# NavCom_Board_1.net
KiCad netlist of a schematic drawn in EAGLE
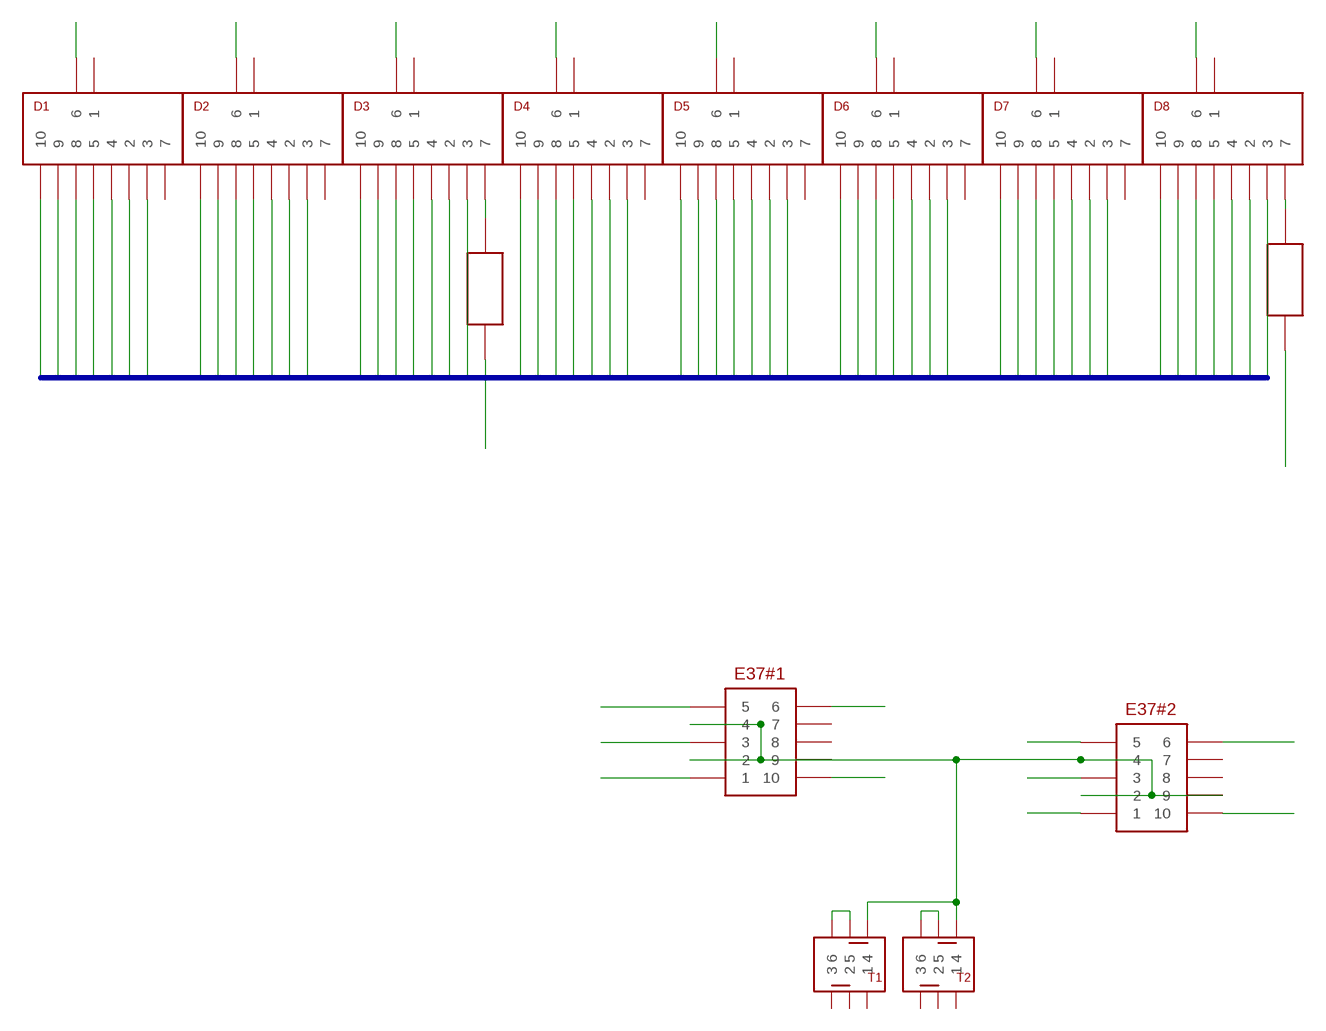
[diagram p0: schematic, sheet 1, part 1 of 2]
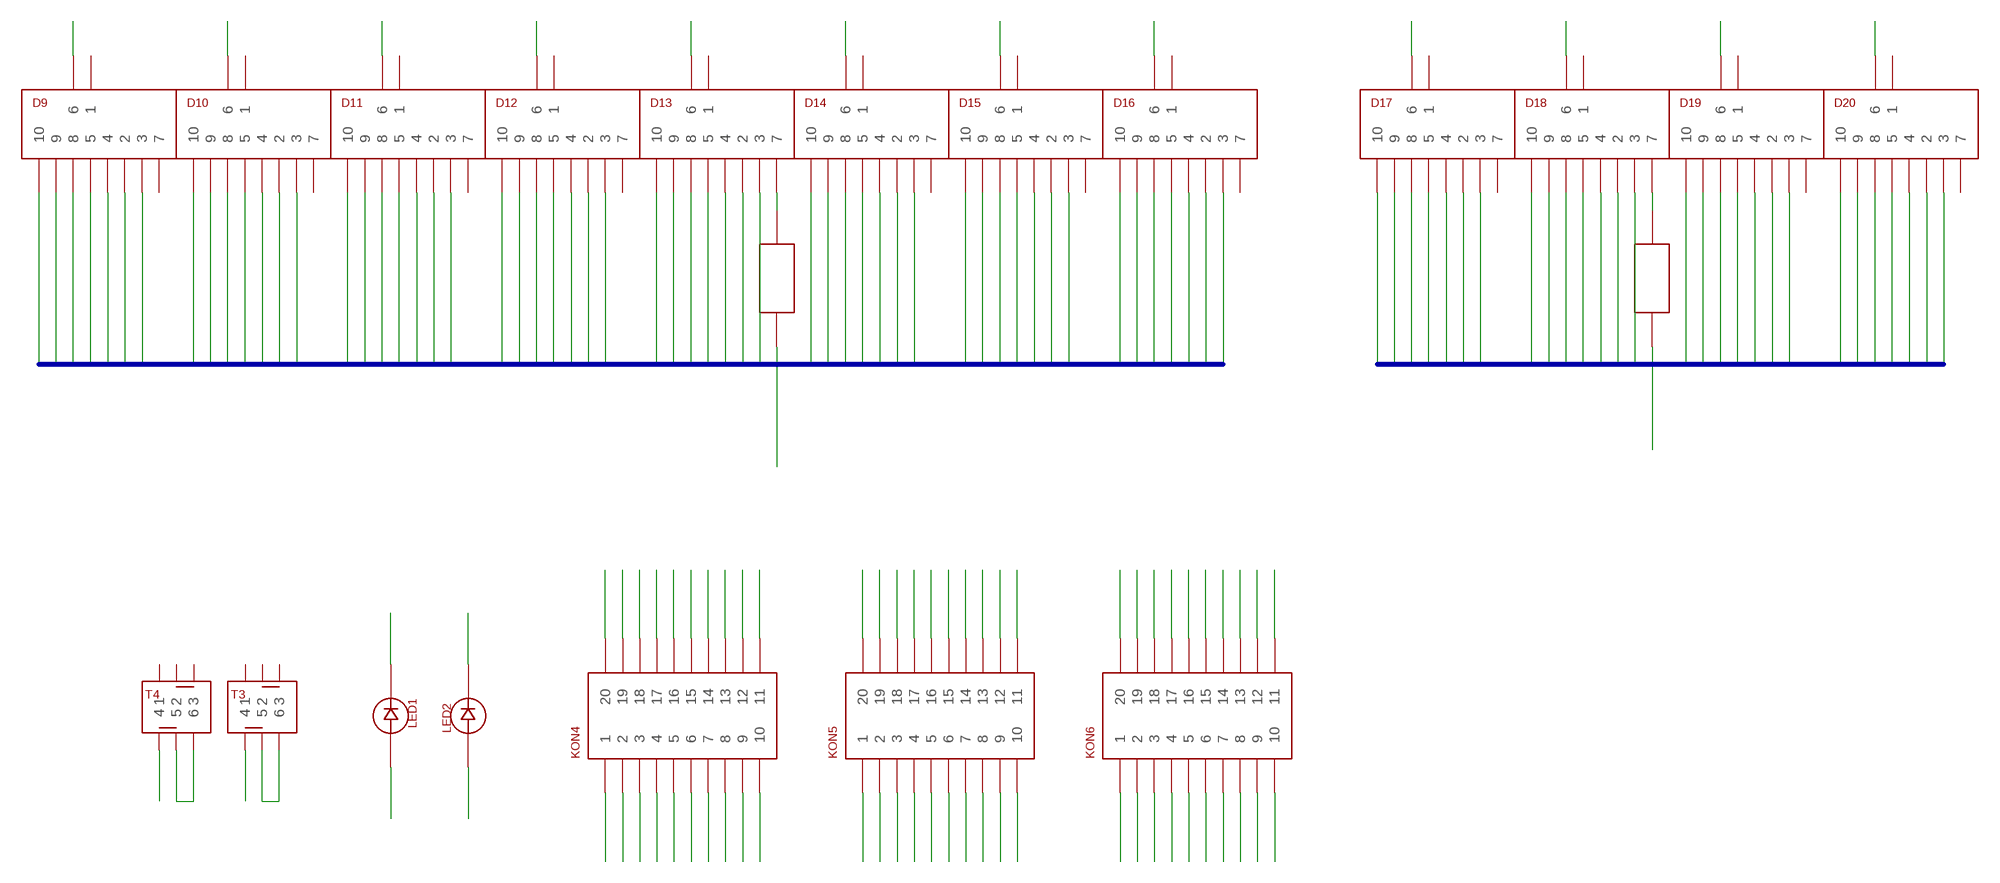
[diagram p1: schematic, sheet 1, part 2 of 2]

(export (version "E")
  (design (tool "Eeschema 10.0.6"))
  (components
    (comp (ref "D1")
      (value "SA3611EWA")
      (footprint "eagle-import:SA3611EWA")
      (libsource (lib "eagle-import") (part "SA3611EWA"))
    )
    (comp (ref "D2")
      (value "SA3611EWA")
      (footprint "eagle-import:SA3611EWA")
      (libsource (lib "eagle-import") (part "SA3611EWA"))
    )
    (comp (ref "D3")
      (value "SA3611EWA")
      (footprint "eagle-import:SA3611EWA")
      (libsource (lib "eagle-import") (part "SA3611EWA"))
    )
    (comp (ref "D4")
      (value "SA3611EWA")
      (footprint "eagle-import:SA3611EWA")
      (libsource (lib "eagle-import") (part "SA3611EWA"))
    )
    (comp (ref "D5")
      (value "SA3611EWA")
      (footprint "eagle-import:SA3611EWA")
      (libsource (lib "eagle-import") (part "SA3611EWA"))
    )
    (comp (ref "D6")
      (value "SA3611EWA")
      (footprint "eagle-import:SA3611EWA")
      (libsource (lib "eagle-import") (part "SA3611EWA"))
    )
    (comp (ref "D7")
      (value "SA3611EWA")
      (footprint "eagle-import:SA3611EWA")
      (libsource (lib "eagle-import") (part "SA3611EWA"))
    )
    (comp (ref "D8")
      (value "SA3611EWA")
      (footprint "eagle-import:SA3611EWA")
      (libsource (lib "eagle-import") (part "SA3611EWA"))
    )
    (comp (ref "D9")
      (value "SA3611EWA")
      (footprint "eagle-import:SA3611EWA")
      (libsource (lib "eagle-import") (part "SA3611EWA"))
    )
    (comp (ref "D10")
      (value "SA3611EWA")
      (footprint "eagle-import:SA3611EWA")
      (libsource (lib "eagle-import") (part "SA3611EWA"))
    )
    (comp (ref "D11")
      (value "SA3611EWA")
      (footprint "eagle-import:SA3611EWA")
      (libsource (lib "eagle-import") (part "SA3611EWA"))
    )
    (comp (ref "D12")
      (value "SA3611EWA")
      (footprint "eagle-import:SA3611EWA")
      (libsource (lib "eagle-import") (part "SA3611EWA"))
    )
    (comp (ref "D13")
      (value "SA3611EWA")
      (footprint "eagle-import:SA3611EWA")
      (libsource (lib "eagle-import") (part "SA3611EWA"))
    )
    (comp (ref "D14")
      (value "SA3611EWA")
      (footprint "eagle-import:SA3611EWA")
      (libsource (lib "eagle-import") (part "SA3611EWA"))
    )
    (comp (ref "D15")
      (value "SA3611EWA")
      (footprint "eagle-import:SA3611EWA")
      (libsource (lib "eagle-import") (part "SA3611EWA"))
    )
    (comp (ref "D16")
      (value "SA3611EWA")
      (footprint "eagle-import:SA3611EWA")
      (libsource (lib "eagle-import") (part "SA3611EWA"))
    )
    (comp (ref "D17")
      (value "SA3611EWA")
      (footprint "eagle-import:SA3611EWA")
      (libsource (lib "eagle-import") (part "SA3611EWA"))
    )
    (comp (ref "D18")
      (value "SA3611EWA")
      (footprint "eagle-import:SA3611EWA")
      (libsource (lib "eagle-import") (part "SA3611EWA"))
    )
    (comp (ref "D19")
      (value "SA3611EWA")
      (footprint "eagle-import:SA3611EWA")
      (libsource (lib "eagle-import") (part "SA3611EWA"))
    )
    (comp (ref "D20")
      (value "SA3611EWA")
      (footprint "eagle-import:SA3611EWA")
      (libsource (lib "eagle-import") (part "SA3611EWA"))
    )
    (comp (ref "E37#1")
      (value "ELMA_E37")
      (footprint "eagle-import:ELMA_E37")
      (libsource (lib "eagle-import") (part "ELMA_E37"))
    )
    (comp (ref "E37#2")
      (value "ELMA_E37")
      (footprint "eagle-import:ELMA_E37")
      (libsource (lib "eagle-import") (part "ELMA_E37"))
    )
    (comp (ref "KON4")
      (value "LISTA_2X10")
      (footprint "eagle-import:LISTA_2X10")
      (libsource (lib "eagle-import") (part "LISTA_2X10"))
    )
    (comp (ref "KON5")
      (value "LISTA_2X10")
      (footprint "eagle-import:LISTA_2X10")
      (libsource (lib "eagle-import") (part "LISTA_2X10"))
    )
    (comp (ref "KON6")
      (value "LISTA_2X10")
      (footprint "eagle-import:LISTA_2X10")
      (libsource (lib "eagle-import") (part "LISTA_2X10"))
    )
    (comp (ref "LED1")
      (value "LED_5MM")
      (footprint "eagle-import:LED_5MM")
      (libsource (lib "eagle-import") (part "LED_5MM"))
    )
    (comp (ref "LED2")
      (value "LED_5MM")
      (footprint "eagle-import:LED_5MM")
      (libsource (lib "eagle-import") (part "LED_5MM"))
    )
    (comp (ref "T1")
      (value "P1-0S")
      (footprint "eagle-import:P1-0S")
      (libsource (lib "eagle-import") (part "P1-0S"))
    )
    (comp (ref "T2")
      (value "P1-0S")
      (footprint "eagle-import:P1-0S")
      (libsource (lib "eagle-import") (part "P1-0S"))
    )
    (comp (ref "T3")
      (value "P1-0S")
      (footprint "eagle-import:P1-0S")
      (libsource (lib "eagle-import") (part "P1-0S"))
    )
    (comp (ref "T4")
      (value "P1-0S")
      (footprint "eagle-import:P1-0S")
      (libsource (lib "eagle-import") (part "P1-0S"))
    )
    (comp (ref "U$1")
      (value "REZISTOR")
      (footprint "eagle-import:REZISTOR")
      (libsource (lib "eagle-import") (part "REZISTOR"))
    )
    (comp (ref "U$2")
      (value "REZISTOR")
      (footprint "eagle-import:REZISTOR")
      (libsource (lib "eagle-import") (part "REZISTOR"))
    )
    (comp (ref "U$3")
      (value "REZISTOR")
      (footprint "eagle-import:REZISTOR")
      (libsource (lib "eagle-import") (part "REZISTOR"))
    )
    (comp (ref "U$4")
      (value "REZISTOR")
      (footprint "eagle-import:REZISTOR")
      (libsource (lib "eagle-import") (part "REZISTOR"))
    )
  )
  (nets
    (net (code "1") (name "/D1") (class "Default")
      (node (ref "D1") (pin "6") (pinfunction "6_6") (pintype "bidirectional"))
      (node (ref "KON4") (pin "1") (pinfunction "1_1") (pintype "bidirectional"))
    )
    (net (code "2") (name "/D2") (class "Default")
      (node (ref "D2") (pin "6") (pinfunction "6_6") (pintype "bidirectional"))
      (node (ref "KON4") (pin "2") (pinfunction "2_2") (pintype "bidirectional"))
    )
    (net (code "3") (name "/D3") (class "Default")
      (node (ref "D3") (pin "6") (pinfunction "6_6") (pintype "bidirectional"))
      (node (ref "KON4") (pin "9") (pinfunction "9_9") (pintype "bidirectional"))
    )
    (net (code "4") (name "/D4") (class "Default")
      (node (ref "D4") (pin "6") (pinfunction "6_6") (pintype "bidirectional"))
      (node (ref "KON4") (pin "6") (pinfunction "6_6") (pintype "bidirectional"))
    )
    (net (code "5") (name "/D5") (class "Default")
      (node (ref "D5") (pin "6") (pinfunction "6_6") (pintype "bidirectional"))
      (node (ref "KON4") (pin "3") (pinfunction "3_3") (pintype "bidirectional"))
    )
    (net (code "6") (name "/D6") (class "Default")
      (node (ref "D6") (pin "6") (pinfunction "6_6") (pintype "bidirectional"))
      (node (ref "KON4") (pin "8") (pinfunction "8_8") (pintype "bidirectional"))
    )
    (net (code "7") (name "/D7") (class "Default")
      (node (ref "D7") (pin "6") (pinfunction "6_6") (pintype "bidirectional"))
      (node (ref "KON4") (pin "7") (pinfunction "7_7") (pintype "bidirectional"))
    )
    (net (code "8") (name "/D8") (class "Default")
      (node (ref "D8") (pin "6") (pinfunction "6_6") (pintype "bidirectional"))
      (node (ref "KON4") (pin "4") (pinfunction "4_4") (pintype "bidirectional"))
    )
    (net (code "9") (name "/D9") (class "Default")
      (node (ref "D9") (pin "6") (pinfunction "6_6") (pintype "bidirectional"))
      (node (ref "KON5") (pin "1") (pinfunction "1_1") (pintype "bidirectional"))
    )
    (net (code "10") (name "/D10") (class "Default")
      (node (ref "D10") (pin "6") (pinfunction "6_6") (pintype "bidirectional"))
      (node (ref "KON5") (pin "2") (pinfunction "2_2") (pintype "bidirectional"))
    )
    (net (code "11") (name "/D11") (class "Default")
      (node (ref "D11") (pin "6") (pinfunction "6_6") (pintype "bidirectional"))
      (node (ref "KON5") (pin "9") (pinfunction "9_9") (pintype "bidirectional"))
    )
    (net (code "12") (name "/D12") (class "Default")
      (node (ref "D12") (pin "6") (pinfunction "6_6") (pintype "bidirectional"))
      (node (ref "KON5") (pin "6") (pinfunction "6_6") (pintype "bidirectional"))
    )
    (net (code "13") (name "/D13") (class "Default")
      (node (ref "D13") (pin "6") (pinfunction "6_6") (pintype "bidirectional"))
      (node (ref "KON5") (pin "3") (pinfunction "3_3") (pintype "bidirectional"))
    )
    (net (code "14") (name "/D14") (class "Default")
      (node (ref "D14") (pin "6") (pinfunction "6_6") (pintype "bidirectional"))
      (node (ref "KON5") (pin "8") (pinfunction "8_8") (pintype "bidirectional"))
    )
    (net (code "15") (name "/D15") (class "Default")
      (node (ref "D15") (pin "6") (pinfunction "6_6") (pintype "bidirectional"))
      (node (ref "KON5") (pin "7") (pinfunction "7_7") (pintype "bidirectional"))
    )
    (net (code "16") (name "/D16") (class "Default")
      (node (ref "D16") (pin "6") (pinfunction "6_6") (pintype "bidirectional"))
      (node (ref "KON5") (pin "4") (pinfunction "4_4") (pintype "bidirectional"))
    )
    (net (code "17") (name "/D17") (class "Default")
      (node (ref "D17") (pin "6") (pinfunction "6_6") (pintype "bidirectional"))
      (node (ref "KON6") (pin "1") (pinfunction "1_1") (pintype "bidirectional"))
    )
    (net (code "18") (name "/D18") (class "Default")
      (node (ref "D18") (pin "6") (pinfunction "6_6") (pintype "bidirectional"))
      (node (ref "KON6") (pin "2") (pinfunction "2_2") (pintype "bidirectional"))
    )
    (net (code "19") (name "/D19") (class "Default")
      (node (ref "D19") (pin "6") (pinfunction "6_6") (pintype "bidirectional"))
      (node (ref "KON6") (pin "9") (pinfunction "9_9") (pintype "bidirectional"))
    )
    (net (code "20") (name "/D20") (class "Default")
      (node (ref "D20") (pin "6") (pinfunction "6_6") (pintype "bidirectional"))
      (node (ref "KON6") (pin "6") (pinfunction "6_6") (pintype "bidirectional"))
    )
    (net (code "21") (name "/DRIVER1_SEG2") (class "Default")
      (node (ref "D1") (pin "2") (pinfunction "2_2") (pintype "bidirectional"))
      (node (ref "D2") (pin "2") (pinfunction "2_2") (pintype "bidirectional"))
      (node (ref "D3") (pin "2") (pinfunction "2_2") (pintype "bidirectional"))
      (node (ref "D4") (pin "2") (pinfunction "2_2") (pintype "bidirectional"))
      (node (ref "D5") (pin "2") (pinfunction "2_2") (pintype "bidirectional"))
      (node (ref "D6") (pin "2") (pinfunction "2_2") (pintype "bidirectional"))
      (node (ref "D7") (pin "2") (pinfunction "2_2") (pintype "bidirectional"))
      (node (ref "D8") (pin "2") (pinfunction "2_2") (pintype "bidirectional"))
      (node (ref "KON4") (pin "10") (pinfunction "10_10") (pintype "bidirectional"))
    )
    (net (code "22") (name "/DRIVER1_SEG3") (class "Default")
      (node (ref "D1") (pin "3") (pinfunction "3_3") (pintype "bidirectional"))
      (node (ref "D2") (pin "3") (pinfunction "3_3") (pintype "bidirectional"))
      (node (ref "D3") (pin "3") (pinfunction "3_3") (pintype "bidirectional"))
      (node (ref "D4") (pin "3") (pinfunction "3_3") (pintype "bidirectional"))
      (node (ref "D5") (pin "3") (pinfunction "3_3") (pintype "bidirectional"))
      (node (ref "D6") (pin "3") (pinfunction "3_3") (pintype "bidirectional"))
      (node (ref "D7") (pin "3") (pinfunction "3_3") (pintype "bidirectional"))
      (node (ref "D8") (pin "3") (pinfunction "3_3") (pintype "bidirectional"))
      (node (ref "KON4") (pin "12") (pinfunction "12_12") (pintype "bidirectional"))
    )
    (net (code "23") (name "/DRIVER1_SEG4") (class "Default")
      (node (ref "D1") (pin "4") (pinfunction "4_4") (pintype "bidirectional"))
      (node (ref "D2") (pin "4") (pinfunction "4_4") (pintype "bidirectional"))
      (node (ref "D3") (pin "4") (pinfunction "4_4") (pintype "bidirectional"))
      (node (ref "D4") (pin "4") (pinfunction "4_4") (pintype "bidirectional"))
      (node (ref "D5") (pin "4") (pinfunction "4_4") (pintype "bidirectional"))
      (node (ref "D6") (pin "4") (pinfunction "4_4") (pintype "bidirectional"))
      (node (ref "D7") (pin "4") (pinfunction "4_4") (pintype "bidirectional"))
      (node (ref "D8") (pin "4") (pinfunction "4_4") (pintype "bidirectional"))
      (node (ref "KON4") (pin "15") (pinfunction "15_15") (pintype "bidirectional"))
    )
    (net (code "24") (name "/DRIVER1_SEG5") (class "Default")
      (node (ref "D1") (pin "5") (pinfunction "5_5") (pintype "bidirectional"))
      (node (ref "D2") (pin "5") (pinfunction "5_5") (pintype "bidirectional"))
      (node (ref "D3") (pin "5") (pinfunction "5_5") (pintype "bidirectional"))
      (node (ref "D4") (pin "5") (pinfunction "5_5") (pintype "bidirectional"))
      (node (ref "D5") (pin "5") (pinfunction "5_5") (pintype "bidirectional"))
      (node (ref "D6") (pin "5") (pinfunction "5_5") (pintype "bidirectional"))
      (node (ref "D7") (pin "5") (pinfunction "5_5") (pintype "bidirectional"))
      (node (ref "D8") (pin "5") (pinfunction "5_5") (pintype "bidirectional"))
      (node (ref "KON4") (pin "16") (pinfunction "16_16") (pintype "bidirectional"))
    )
    (net (code "25") (name "/DRIVER1_SEG8") (class "Default")
      (node (ref "D1") (pin "8") (pinfunction "8_8") (pintype "bidirectional"))
      (node (ref "D2") (pin "8") (pinfunction "8_8") (pintype "bidirectional"))
      (node (ref "D3") (pin "8") (pinfunction "8_8") (pintype "bidirectional"))
      (node (ref "D4") (pin "8") (pinfunction "8_8") (pintype "bidirectional"))
      (node (ref "D5") (pin "8") (pinfunction "8_8") (pintype "bidirectional"))
      (node (ref "D6") (pin "8") (pinfunction "8_8") (pintype "bidirectional"))
      (node (ref "D7") (pin "8") (pinfunction "8_8") (pintype "bidirectional"))
      (node (ref "D8") (pin "8") (pinfunction "8_8") (pintype "bidirectional"))
      (node (ref "KON4") (pin "14") (pinfunction "14_14") (pintype "bidirectional"))
    )
    (net (code "26") (name "/DRIVER1_SEG9") (class "Default")
      (node (ref "D1") (pin "9") (pinfunction "9_9") (pintype "bidirectional"))
      (node (ref "D2") (pin "9") (pinfunction "9_9") (pintype "bidirectional"))
      (node (ref "D3") (pin "9") (pinfunction "9_9") (pintype "bidirectional"))
      (node (ref "D4") (pin "9") (pinfunction "9_9") (pintype "bidirectional"))
      (node (ref "D5") (pin "9") (pinfunction "9_9") (pintype "bidirectional"))
      (node (ref "D6") (pin "9") (pinfunction "9_9") (pintype "bidirectional"))
      (node (ref "D7") (pin "9") (pinfunction "9_9") (pintype "bidirectional"))
      (node (ref "D8") (pin "9") (pinfunction "9_9") (pintype "bidirectional"))
      (node (ref "KON4") (pin "11") (pinfunction "11_11") (pintype "bidirectional"))
    )
    (net (code "27") (name "/DRIVER1_SEG10") (class "Default")
      (node (ref "D1") (pin "10") (pinfunction "10_10") (pintype "bidirectional"))
      (node (ref "D2") (pin "10") (pinfunction "10_10") (pintype "bidirectional"))
      (node (ref "D3") (pin "10") (pinfunction "10_10") (pintype "bidirectional"))
      (node (ref "D4") (pin "10") (pinfunction "10_10") (pintype "bidirectional"))
      (node (ref "D5") (pin "10") (pinfunction "10_10") (pintype "bidirectional"))
      (node (ref "D6") (pin "10") (pinfunction "10_10") (pintype "bidirectional"))
      (node (ref "D7") (pin "10") (pinfunction "10_10") (pintype "bidirectional"))
      (node (ref "D8") (pin "10") (pinfunction "10_10") (pintype "bidirectional"))
      (node (ref "KON4") (pin "13") (pinfunction "13_13") (pintype "bidirectional"))
    )
    (net (code "28") (name "/DRIVER2_SEG2") (class "Default")
      (node (ref "D10") (pin "2") (pinfunction "2_2") (pintype "bidirectional"))
      (node (ref "D11") (pin "2") (pinfunction "2_2") (pintype "bidirectional"))
      (node (ref "D12") (pin "2") (pinfunction "2_2") (pintype "bidirectional"))
      (node (ref "D13") (pin "2") (pinfunction "2_2") (pintype "bidirectional"))
      (node (ref "D14") (pin "2") (pinfunction "2_2") (pintype "bidirectional"))
      (node (ref "D15") (pin "2") (pinfunction "2_2") (pintype "bidirectional"))
      (node (ref "D16") (pin "2") (pinfunction "2_2") (pintype "bidirectional"))
      (node (ref "D9") (pin "2") (pinfunction "2_2") (pintype "bidirectional"))
      (node (ref "KON5") (pin "10") (pinfunction "10_10") (pintype "bidirectional"))
    )
    (net (code "29") (name "/DRIVER2_SEG3") (class "Default")
      (node (ref "D10") (pin "3") (pinfunction "3_3") (pintype "bidirectional"))
      (node (ref "D11") (pin "3") (pinfunction "3_3") (pintype "bidirectional"))
      (node (ref "D12") (pin "3") (pinfunction "3_3") (pintype "bidirectional"))
      (node (ref "D13") (pin "3") (pinfunction "3_3") (pintype "bidirectional"))
      (node (ref "D14") (pin "3") (pinfunction "3_3") (pintype "bidirectional"))
      (node (ref "D15") (pin "3") (pinfunction "3_3") (pintype "bidirectional"))
      (node (ref "D16") (pin "3") (pinfunction "3_3") (pintype "bidirectional"))
      (node (ref "D9") (pin "3") (pinfunction "3_3") (pintype "bidirectional"))
      (node (ref "KON5") (pin "12") (pinfunction "12_12") (pintype "bidirectional"))
    )
    (net (code "30") (name "/DRIVER2_SEG4") (class "Default")
      (node (ref "D10") (pin "4") (pinfunction "4_4") (pintype "bidirectional"))
      (node (ref "D11") (pin "4") (pinfunction "4_4") (pintype "bidirectional"))
      (node (ref "D12") (pin "4") (pinfunction "4_4") (pintype "bidirectional"))
      (node (ref "D13") (pin "4") (pinfunction "4_4") (pintype "bidirectional"))
      (node (ref "D14") (pin "4") (pinfunction "4_4") (pintype "bidirectional"))
      (node (ref "D15") (pin "4") (pinfunction "4_4") (pintype "bidirectional"))
      (node (ref "D16") (pin "4") (pinfunction "4_4") (pintype "bidirectional"))
      (node (ref "D9") (pin "4") (pinfunction "4_4") (pintype "bidirectional"))
      (node (ref "KON5") (pin "15") (pinfunction "15_15") (pintype "bidirectional"))
    )
    (net (code "31") (name "/DRIVER2_SEG5") (class "Default")
      (node (ref "D10") (pin "5") (pinfunction "5_5") (pintype "bidirectional"))
      (node (ref "D11") (pin "5") (pinfunction "5_5") (pintype "bidirectional"))
      (node (ref "D12") (pin "5") (pinfunction "5_5") (pintype "bidirectional"))
      (node (ref "D13") (pin "5") (pinfunction "5_5") (pintype "bidirectional"))
      (node (ref "D14") (pin "5") (pinfunction "5_5") (pintype "bidirectional"))
      (node (ref "D15") (pin "5") (pinfunction "5_5") (pintype "bidirectional"))
      (node (ref "D16") (pin "5") (pinfunction "5_5") (pintype "bidirectional"))
      (node (ref "D9") (pin "5") (pinfunction "5_5") (pintype "bidirectional"))
      (node (ref "KON5") (pin "16") (pinfunction "16_16") (pintype "bidirectional"))
    )
    (net (code "32") (name "/DRIVER2_SEG8") (class "Default")
      (node (ref "D10") (pin "8") (pinfunction "8_8") (pintype "bidirectional"))
      (node (ref "D11") (pin "8") (pinfunction "8_8") (pintype "bidirectional"))
      (node (ref "D12") (pin "8") (pinfunction "8_8") (pintype "bidirectional"))
      (node (ref "D13") (pin "8") (pinfunction "8_8") (pintype "bidirectional"))
      (node (ref "D14") (pin "8") (pinfunction "8_8") (pintype "bidirectional"))
      (node (ref "D15") (pin "8") (pinfunction "8_8") (pintype "bidirectional"))
      (node (ref "D16") (pin "8") (pinfunction "8_8") (pintype "bidirectional"))
      (node (ref "D9") (pin "8") (pinfunction "8_8") (pintype "bidirectional"))
      (node (ref "KON5") (pin "14") (pinfunction "14_14") (pintype "bidirectional"))
    )
    (net (code "33") (name "/DRIVER2_SEG9") (class "Default")
      (node (ref "D10") (pin "9") (pinfunction "9_9") (pintype "bidirectional"))
      (node (ref "D11") (pin "9") (pinfunction "9_9") (pintype "bidirectional"))
      (node (ref "D12") (pin "9") (pinfunction "9_9") (pintype "bidirectional"))
      (node (ref "D13") (pin "9") (pinfunction "9_9") (pintype "bidirectional"))
      (node (ref "D14") (pin "9") (pinfunction "9_9") (pintype "bidirectional"))
      (node (ref "D15") (pin "9") (pinfunction "9_9") (pintype "bidirectional"))
      (node (ref "D16") (pin "9") (pinfunction "9_9") (pintype "bidirectional"))
      (node (ref "D9") (pin "9") (pinfunction "9_9") (pintype "bidirectional"))
      (node (ref "KON5") (pin "11") (pinfunction "11_11") (pintype "bidirectional"))
    )
    (net (code "34") (name "/DRIVER2_SEG10") (class "Default")
      (node (ref "D10") (pin "10") (pinfunction "10_10") (pintype "bidirectional"))
      (node (ref "D11") (pin "10") (pinfunction "10_10") (pintype "bidirectional"))
      (node (ref "D12") (pin "10") (pinfunction "10_10") (pintype "bidirectional"))
      (node (ref "D13") (pin "10") (pinfunction "10_10") (pintype "bidirectional"))
      (node (ref "D14") (pin "10") (pinfunction "10_10") (pintype "bidirectional"))
      (node (ref "D15") (pin "10") (pinfunction "10_10") (pintype "bidirectional"))
      (node (ref "D16") (pin "10") (pinfunction "10_10") (pintype "bidirectional"))
      (node (ref "D9") (pin "10") (pinfunction "10_10") (pintype "bidirectional"))
      (node (ref "KON5") (pin "13") (pinfunction "13_13") (pintype "bidirectional"))
    )
    (net (code "35") (name "/DRIVER3_SEG2") (class "Default")
      (node (ref "D17") (pin "2") (pinfunction "2_2") (pintype "bidirectional"))
      (node (ref "D18") (pin "2") (pinfunction "2_2") (pintype "bidirectional"))
      (node (ref "D19") (pin "2") (pinfunction "2_2") (pintype "bidirectional"))
      (node (ref "D20") (pin "2") (pinfunction "2_2") (pintype "bidirectional"))
      (node (ref "KON6") (pin "10") (pinfunction "10_10") (pintype "bidirectional"))
    )
    (net (code "36") (name "/DRIVER3_SEG3") (class "Default")
      (node (ref "D17") (pin "3") (pinfunction "3_3") (pintype "bidirectional"))
      (node (ref "D18") (pin "3") (pinfunction "3_3") (pintype "bidirectional"))
      (node (ref "D19") (pin "3") (pinfunction "3_3") (pintype "bidirectional"))
      (node (ref "D20") (pin "3") (pinfunction "3_3") (pintype "bidirectional"))
      (node (ref "KON6") (pin "12") (pinfunction "12_12") (pintype "bidirectional"))
    )
    (net (code "37") (name "/DRIVER3_SEG4") (class "Default")
      (node (ref "D17") (pin "4") (pinfunction "4_4") (pintype "bidirectional"))
      (node (ref "D18") (pin "4") (pinfunction "4_4") (pintype "bidirectional"))
      (node (ref "D19") (pin "4") (pinfunction "4_4") (pintype "bidirectional"))
      (node (ref "D20") (pin "4") (pinfunction "4_4") (pintype "bidirectional"))
      (node (ref "KON6") (pin "15") (pinfunction "15_15") (pintype "bidirectional"))
    )
    (net (code "38") (name "/DRIVER3_SEG5") (class "Default")
      (node (ref "D17") (pin "5") (pinfunction "5_5") (pintype "bidirectional"))
      (node (ref "D18") (pin "5") (pinfunction "5_5") (pintype "bidirectional"))
      (node (ref "D19") (pin "5") (pinfunction "5_5") (pintype "bidirectional"))
      (node (ref "D20") (pin "5") (pinfunction "5_5") (pintype "bidirectional"))
      (node (ref "KON6") (pin "16") (pinfunction "16_16") (pintype "bidirectional"))
      (node (ref "LED1") (pin "P$2") (pinfunction "P$2_P$2") (pintype "bidirectional"))
      (node (ref "LED2") (pin "P$2") (pinfunction "P$2_P$2") (pintype "bidirectional"))
    )
    (net (code "39") (name "/DRIVER3_SEG8") (class "Default")
      (node (ref "D17") (pin "8") (pinfunction "8_8") (pintype "bidirectional"))
      (node (ref "D18") (pin "8") (pinfunction "8_8") (pintype "bidirectional"))
      (node (ref "D19") (pin "8") (pinfunction "8_8") (pintype "bidirectional"))
      (node (ref "D20") (pin "8") (pinfunction "8_8") (pintype "bidirectional"))
      (node (ref "KON6") (pin "14") (pinfunction "14_14") (pintype "bidirectional"))
    )
    (net (code "40") (name "/DRIVER3_SEG9") (class "Default")
      (node (ref "D17") (pin "9") (pinfunction "9_9") (pintype "bidirectional"))
      (node (ref "D18") (pin "9") (pinfunction "9_9") (pintype "bidirectional"))
      (node (ref "D19") (pin "9") (pinfunction "9_9") (pintype "bidirectional"))
      (node (ref "D20") (pin "9") (pinfunction "9_9") (pintype "bidirectional"))
      (node (ref "KON6") (pin "11") (pinfunction "11_11") (pintype "bidirectional"))
    )
    (net (code "41") (name "/DRIVER3_SEG10") (class "Default")
      (node (ref "D17") (pin "10") (pinfunction "10_10") (pintype "bidirectional"))
      (node (ref "D18") (pin "10") (pinfunction "10_10") (pintype "bidirectional"))
      (node (ref "D19") (pin "10") (pinfunction "10_10") (pintype "bidirectional"))
      (node (ref "D20") (pin "10") (pinfunction "10_10") (pintype "bidirectional"))
      (node (ref "KON6") (pin "13") (pinfunction "13_13") (pintype "bidirectional"))
    )
    (net (code "42") (name "/E37#1_1") (class "Default")
      (node (ref "E37#1") (pin "1") (pinfunction "1_1") (pintype "bidirectional"))
      (node (ref "KON4") (pin "17") (pinfunction "17_17") (pintype "bidirectional"))
    )
    (net (code "43") (name "/E37#1_3") (class "Default")
      (node (ref "E37#1") (pin "3") (pinfunction "3_3") (pintype "bidirectional"))
      (node (ref "KON4") (pin "18") (pinfunction "18_18") (pintype "bidirectional"))
    )
    (net (code "44") (name "/E37#1_5") (class "Default")
      (node (ref "E37#1") (pin "5") (pinfunction "5_5") (pintype "bidirectional"))
      (node (ref "KON4") (pin "20") (pinfunction "20_20") (pintype "bidirectional"))
    )
    (net (code "45") (name "/E37#1_6") (class "Default")
      (node (ref "E37#1") (pin "6") (pinfunction "6_6") (pintype "bidirectional"))
      (node (ref "KON4") (pin "19") (pinfunction "19_19") (pintype "bidirectional"))
    )
    (net (code "46") (name "/E37#1_10") (class "Default")
      (node (ref "E37#1") (pin "10") (pinfunction "10_10") (pintype "bidirectional"))
      (node (ref "KON4") (pin "5") (pinfunction "5_5") (pintype "bidirectional"))
    )
    (net (code "47") (name "/E37#2_1") (class "Default")
      (node (ref "E37#2") (pin "1") (pinfunction "1_1") (pintype "bidirectional"))
      (node (ref "KON6") (pin "17") (pinfunction "17_17") (pintype "bidirectional"))
    )
    (net (code "48") (name "/E37#2_3") (class "Default")
      (node (ref "E37#2") (pin "3") (pinfunction "3_3") (pintype "bidirectional"))
      (node (ref "KON6") (pin "18") (pinfunction "18_18") (pintype "bidirectional"))
    )
    (net (code "49") (name "/E37#2_5") (class "Default")
      (node (ref "E37#2") (pin "5") (pinfunction "5_5") (pintype "bidirectional"))
      (node (ref "KON6") (pin "20") (pinfunction "20_20") (pintype "bidirectional"))
    )
    (net (code "50") (name "/E37#2_6") (class "Default")
      (node (ref "E37#2") (pin "6") (pinfunction "6_6") (pintype "bidirectional"))
      (node (ref "KON6") (pin "19") (pinfunction "19_19") (pintype "bidirectional"))
    )
    (net (code "51") (name "/E37#2_10") (class "Default")
      (node (ref "E37#2") (pin "10") (pinfunction "10_10") (pintype "bidirectional"))
      (node (ref "KON6") (pin "5") (pinfunction "5_5") (pintype "bidirectional"))
    )
    (net (code "52") (name "/GND") (class "Default")
      (node (ref "E37#1") (pin "2") (pinfunction "2_2") (pintype "bidirectional"))
      (node (ref "E37#1") (pin "4") (pinfunction "4_4") (pintype "bidirectional"))
      (node (ref "E37#1") (pin "9") (pinfunction "9_9") (pintype "bidirectional"))
      (node (ref "E37#2") (pin "2") (pinfunction "2_2") (pintype "bidirectional"))
      (node (ref "E37#2") (pin "4") (pinfunction "4_4") (pintype "bidirectional"))
      (node (ref "E37#2") (pin "9") (pinfunction "9_9") (pintype "bidirectional"))
      (node (ref "KON5") (pin "5") (pinfunction "5_5") (pintype "bidirectional"))
      (node (ref "T1") (pin "4") (pinfunction "4_4") (pintype "bidirectional"))
      (node (ref "T2") (pin "4") (pinfunction "4_4") (pintype "bidirectional"))
      (node (ref "T3") (pin "5") (pinfunction "5_5") (pintype "bidirectional"))
      (node (ref "T3") (pin "6") (pinfunction "6_6") (pintype "bidirectional"))
      (node (ref "T4") (pin "5") (pinfunction "5_5") (pintype "bidirectional"))
      (node (ref "T4") (pin "6") (pinfunction "6_6") (pintype "bidirectional"))
      (node (ref "U$1") (pin "P$1") (pinfunction "P$1_P$1") (pintype "bidirectional"))
      (node (ref "U$2") (pin "P$1") (pinfunction "P$1_P$1") (pintype "bidirectional"))
      (node (ref "U$3") (pin "P$1") (pinfunction "P$1_P$1") (pintype "bidirectional"))
      (node (ref "U$4") (pin "P$1") (pinfunction "P$1_P$1") (pintype "bidirectional"))
    )
    (net (code "53") (name "/LED1") (class "Default")
      (node (ref "KON6") (pin "3") (pinfunction "3_3") (pintype "bidirectional"))
      (node (ref "LED1") (pin "P$1") (pinfunction "P$1_P$1") (pintype "bidirectional"))
    )
    (net (code "54") (name "/LED2") (class "Default")
      (node (ref "KON6") (pin "8") (pinfunction "8_8") (pintype "bidirectional"))
      (node (ref "LED2") (pin "P$1") (pinfunction "P$1_P$1") (pintype "bidirectional"))
    )
    (net (code "55") (name "/T1") (class "Default")
      (node (ref "KON5") (pin "20") (pinfunction "20_20") (pintype "bidirectional"))
      (node (ref "T1") (pin "5") (pinfunction "5_5") (pintype "bidirectional"))
      (node (ref "T1") (pin "6") (pinfunction "6_6") (pintype "bidirectional"))
    )
    (net (code "56") (name "/T2") (class "Default")
      (node (ref "KON5") (pin "19") (pinfunction "19_19") (pintype "bidirectional"))
      (node (ref "T2") (pin "5") (pinfunction "5_5") (pintype "bidirectional"))
      (node (ref "T2") (pin "6") (pinfunction "6_6") (pintype "bidirectional"))
    )
    (net (code "57") (name "/T3") (class "Default")
      (node (ref "KON5") (pin "18") (pinfunction "18_18") (pintype "bidirectional"))
      (node (ref "T3") (pin "4") (pinfunction "4_4") (pintype "bidirectional"))
    )
    (net (code "58") (name "/T4") (class "Default")
      (node (ref "KON5") (pin "17") (pinfunction "17_17") (pintype "bidirectional"))
      (node (ref "T4") (pin "4") (pinfunction "4_4") (pintype "bidirectional"))
    )
    (net (code "59") (name "Net-(D3-Pad7)") (class "Default")
      (node (ref "D3") (pin "7") (pinfunction "7_7") (pintype "bidirectional"))
      (node (ref "U$4") (pin "P$2") (pinfunction "P$2_P$2") (pintype "bidirectional"))
    )
    (net (code "60") (name "Net-(D8-Pad7)") (class "Default")
      (node (ref "D8") (pin "7") (pinfunction "7_7") (pintype "bidirectional"))
      (node (ref "U$3") (pin "P$2") (pinfunction "P$2_P$2") (pintype "bidirectional"))
    )
    (net (code "61") (name "Net-(D13-Pad7)") (class "Default")
      (node (ref "D13") (pin "7") (pinfunction "7_7") (pintype "bidirectional"))
      (node (ref "U$1") (pin "P$2") (pinfunction "P$2_P$2") (pintype "bidirectional"))
    )
    (net (code "62") (name "Net-(D18-Pad7)") (class "Default")
      (node (ref "D18") (pin "7") (pinfunction "7_7") (pintype "bidirectional"))
      (node (ref "U$2") (pin "P$2") (pinfunction "P$2_P$2") (pintype "bidirectional"))
    )
    (net (code "63") (name "unconnected-(D1-Pad1)") (class "Default")
      (node (ref "D1") (pin "1") (pinfunction "1_1") (pintype "bidirectional"))
    )
    (net (code "64") (name "unconnected-(D1-Pad7)") (class "Default")
      (node (ref "D1") (pin "7") (pinfunction "7_7") (pintype "bidirectional"))
    )
    (net (code "65") (name "unconnected-(D2-Pad1)") (class "Default")
      (node (ref "D2") (pin "1") (pinfunction "1_1") (pintype "bidirectional"))
    )
    (net (code "66") (name "unconnected-(D2-Pad7)") (class "Default")
      (node (ref "D2") (pin "7") (pinfunction "7_7") (pintype "bidirectional"))
    )
    (net (code "67") (name "unconnected-(D3-Pad1)") (class "Default")
      (node (ref "D3") (pin "1") (pinfunction "1_1") (pintype "bidirectional"))
    )
    (net (code "68") (name "unconnected-(D4-Pad1)") (class "Default")
      (node (ref "D4") (pin "1") (pinfunction "1_1") (pintype "bidirectional"))
    )
    (net (code "69") (name "unconnected-(D4-Pad7)") (class "Default")
      (node (ref "D4") (pin "7") (pinfunction "7_7") (pintype "bidirectional"))
    )
    (net (code "70") (name "unconnected-(D5-Pad1)") (class "Default")
      (node (ref "D5") (pin "1") (pinfunction "1_1") (pintype "bidirectional"))
    )
    (net (code "71") (name "unconnected-(D5-Pad7)") (class "Default")
      (node (ref "D5") (pin "7") (pinfunction "7_7") (pintype "bidirectional"))
    )
    (net (code "72") (name "unconnected-(D6-Pad1)") (class "Default")
      (node (ref "D6") (pin "1") (pinfunction "1_1") (pintype "bidirectional"))
    )
    (net (code "73") (name "unconnected-(D6-Pad7)") (class "Default")
      (node (ref "D6") (pin "7") (pinfunction "7_7") (pintype "bidirectional"))
    )
    (net (code "74") (name "unconnected-(D7-Pad1)") (class "Default")
      (node (ref "D7") (pin "1") (pinfunction "1_1") (pintype "bidirectional"))
    )
    (net (code "75") (name "unconnected-(D7-Pad7)") (class "Default")
      (node (ref "D7") (pin "7") (pinfunction "7_7") (pintype "bidirectional"))
    )
    (net (code "76") (name "unconnected-(D8-Pad1)") (class "Default")
      (node (ref "D8") (pin "1") (pinfunction "1_1") (pintype "bidirectional"))
    )
    (net (code "77") (name "unconnected-(D9-Pad1)") (class "Default")
      (node (ref "D9") (pin "1") (pinfunction "1_1") (pintype "bidirectional"))
    )
    (net (code "78") (name "unconnected-(D9-Pad7)") (class "Default")
      (node (ref "D9") (pin "7") (pinfunction "7_7") (pintype "bidirectional"))
    )
    (net (code "79") (name "unconnected-(D10-Pad1)") (class "Default")
      (node (ref "D10") (pin "1") (pinfunction "1_1") (pintype "bidirectional"))
    )
    (net (code "80") (name "unconnected-(D10-Pad7)") (class "Default")
      (node (ref "D10") (pin "7") (pinfunction "7_7") (pintype "bidirectional"))
    )
    (net (code "81") (name "unconnected-(D11-Pad1)") (class "Default")
      (node (ref "D11") (pin "1") (pinfunction "1_1") (pintype "bidirectional"))
    )
    (net (code "82") (name "unconnected-(D11-Pad7)") (class "Default")
      (node (ref "D11") (pin "7") (pinfunction "7_7") (pintype "bidirectional"))
    )
    (net (code "83") (name "unconnected-(D12-Pad1)") (class "Default")
      (node (ref "D12") (pin "1") (pinfunction "1_1") (pintype "bidirectional"))
    )
    (net (code "84") (name "unconnected-(D12-Pad7)") (class "Default")
      (node (ref "D12") (pin "7") (pinfunction "7_7") (pintype "bidirectional"))
    )
    (net (code "85") (name "unconnected-(D13-Pad1)") (class "Default")
      (node (ref "D13") (pin "1") (pinfunction "1_1") (pintype "bidirectional"))
    )
    (net (code "86") (name "unconnected-(D14-Pad1)") (class "Default")
      (node (ref "D14") (pin "1") (pinfunction "1_1") (pintype "bidirectional"))
    )
    (net (code "87") (name "unconnected-(D14-Pad7)") (class "Default")
      (node (ref "D14") (pin "7") (pinfunction "7_7") (pintype "bidirectional"))
    )
    (net (code "88") (name "unconnected-(D15-Pad1)") (class "Default")
      (node (ref "D15") (pin "1") (pinfunction "1_1") (pintype "bidirectional"))
    )
    (net (code "89") (name "unconnected-(D15-Pad7)") (class "Default")
      (node (ref "D15") (pin "7") (pinfunction "7_7") (pintype "bidirectional"))
    )
    (net (code "90") (name "unconnected-(D16-Pad1)") (class "Default")
      (node (ref "D16") (pin "1") (pinfunction "1_1") (pintype "bidirectional"))
    )
    (net (code "91") (name "unconnected-(D16-Pad7)") (class "Default")
      (node (ref "D16") (pin "7") (pinfunction "7_7") (pintype "bidirectional"))
    )
    (net (code "92") (name "unconnected-(D17-Pad1)") (class "Default")
      (node (ref "D17") (pin "1") (pinfunction "1_1") (pintype "bidirectional"))
    )
    (net (code "93") (name "unconnected-(D17-Pad7)") (class "Default")
      (node (ref "D17") (pin "7") (pinfunction "7_7") (pintype "bidirectional"))
    )
    (net (code "94") (name "unconnected-(D18-Pad1)") (class "Default")
      (node (ref "D18") (pin "1") (pinfunction "1_1") (pintype "bidirectional"))
    )
    (net (code "95") (name "unconnected-(D19-Pad1)") (class "Default")
      (node (ref "D19") (pin "1") (pinfunction "1_1") (pintype "bidirectional"))
    )
    (net (code "96") (name "unconnected-(D19-Pad7)") (class "Default")
      (node (ref "D19") (pin "7") (pinfunction "7_7") (pintype "bidirectional"))
    )
    (net (code "97") (name "unconnected-(D20-Pad1)") (class "Default")
      (node (ref "D20") (pin "1") (pinfunction "1_1") (pintype "bidirectional"))
    )
    (net (code "98") (name "unconnected-(D20-Pad7)") (class "Default")
      (node (ref "D20") (pin "7") (pinfunction "7_7") (pintype "bidirectional"))
    )
    (net (code "99") (name "unconnected-(E37#1-Pad7)") (class "Default")
      (node (ref "E37#1") (pin "7") (pinfunction "7_7") (pintype "bidirectional"))
    )
    (net (code "100") (name "unconnected-(E37#1-Pad8)") (class "Default")
      (node (ref "E37#1") (pin "8") (pinfunction "8_8") (pintype "bidirectional"))
    )
    (net (code "101") (name "unconnected-(E37#2-Pad7)") (class "Default")
      (node (ref "E37#2") (pin "7") (pinfunction "7_7") (pintype "bidirectional"))
    )
    (net (code "102") (name "unconnected-(E37#2-Pad8)") (class "Default")
      (node (ref "E37#2") (pin "8") (pinfunction "8_8") (pintype "bidirectional"))
    )
    (net (code "103") (name "unconnected-(KON6-Pad4)") (class "Default")
      (node (ref "KON6") (pin "4") (pinfunction "4_4") (pintype "bidirectional"))
    )
    (net (code "104") (name "unconnected-(KON6-Pad7)") (class "Default")
      (node (ref "KON6") (pin "7") (pinfunction "7_7") (pintype "bidirectional"))
    )
    (net (code "105") (name "unconnected-(T1-Pad1)") (class "Default")
      (node (ref "T1") (pin "1") (pinfunction "1_1") (pintype "bidirectional"))
    )
    (net (code "106") (name "unconnected-(T1-Pad2)") (class "Default")
      (node (ref "T1") (pin "2") (pinfunction "2_2") (pintype "bidirectional"))
    )
    (net (code "107") (name "unconnected-(T1-Pad3)") (class "Default")
      (node (ref "T1") (pin "3") (pinfunction "3_3") (pintype "bidirectional"))
    )
    (net (code "108") (name "unconnected-(T2-Pad1)") (class "Default")
      (node (ref "T2") (pin "1") (pinfunction "1_1") (pintype "bidirectional"))
    )
    (net (code "109") (name "unconnected-(T2-Pad2)") (class "Default")
      (node (ref "T2") (pin "2") (pinfunction "2_2") (pintype "bidirectional"))
    )
    (net (code "110") (name "unconnected-(T2-Pad3)") (class "Default")
      (node (ref "T2") (pin "3") (pinfunction "3_3") (pintype "bidirectional"))
    )
    (net (code "111") (name "unconnected-(T3-Pad1)") (class "Default")
      (node (ref "T3") (pin "1") (pinfunction "1_1") (pintype "bidirectional"))
    )
    (net (code "112") (name "unconnected-(T3-Pad2)") (class "Default")
      (node (ref "T3") (pin "2") (pinfunction "2_2") (pintype "bidirectional"))
    )
    (net (code "113") (name "unconnected-(T3-Pad3)") (class "Default")
      (node (ref "T3") (pin "3") (pinfunction "3_3") (pintype "bidirectional"))
    )
    (net (code "114") (name "unconnected-(T4-Pad1)") (class "Default")
      (node (ref "T4") (pin "1") (pinfunction "1_1") (pintype "bidirectional"))
    )
    (net (code "115") (name "unconnected-(T4-Pad2)") (class "Default")
      (node (ref "T4") (pin "2") (pinfunction "2_2") (pintype "bidirectional"))
    )
    (net (code "116") (name "unconnected-(T4-Pad3)") (class "Default")
      (node (ref "T4") (pin "3") (pinfunction "3_3") (pintype "bidirectional"))
    )
  )
)
